# AT32F437.net
KiCad netlist of a schematic drawn in EasyEDA
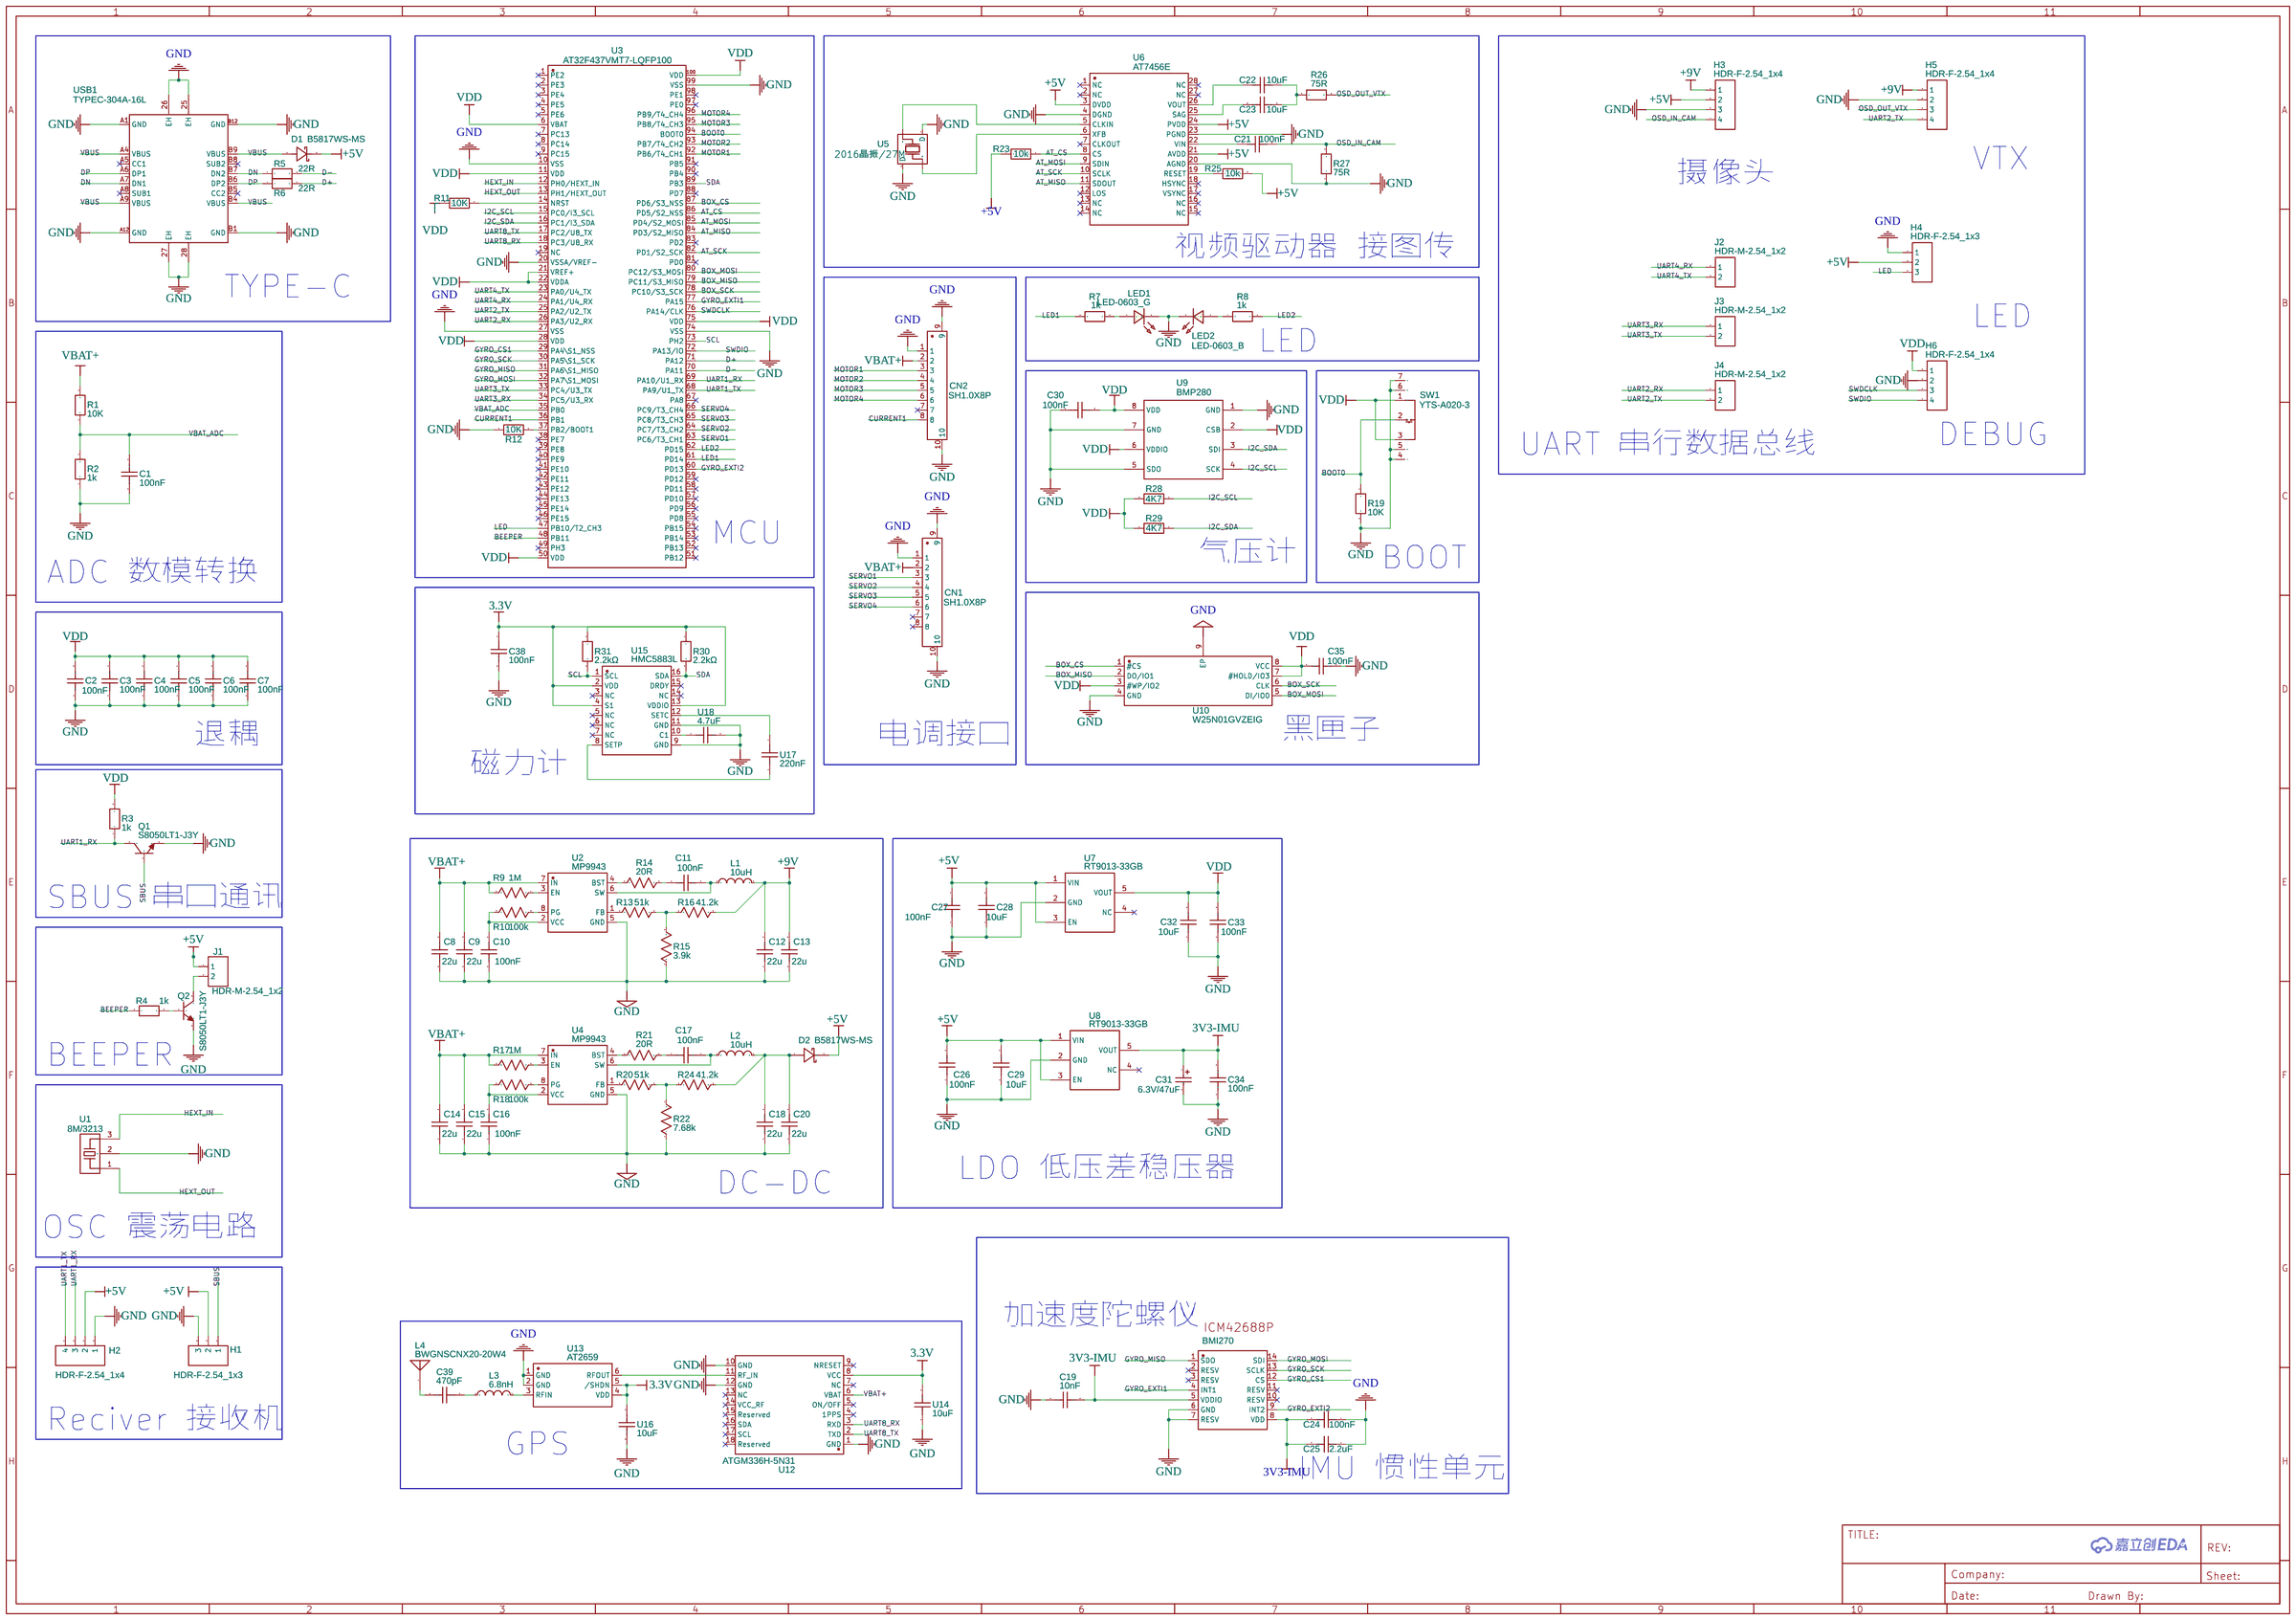
[diagram p0: schematic sheet]

(export (version "E")
  (design (tool "Eeschema 10.0.6"))
  (components
    (comp (ref "C1") (value "100nF") (libsource (lib "") (part "C_0402_US")))
    (comp (ref "C2") (value "100nF") (libsource (lib "") (part "C_0402_US")))
    (comp (ref "C3") (value "100nF") (libsource (lib "") (part "C_0402_US")))
    (comp (ref "C4") (value "100nF") (libsource (lib "") (part "C_0402_US")))
    (comp (ref "C5") (value "100nF") (libsource (lib "") (part "C_0402_US")))
    (comp (ref "C6") (value "100nF") (libsource (lib "") (part "C_0402_US")))
    (comp (ref "C7") (value "100nF") (libsource (lib "") (part "C_0402_US")))
    (comp (ref "C8") (value "22u") (libsource (lib "") (part "C_0201_US")))
    (comp (ref "C9") (value "22u") (libsource (lib "") (part "C_0201_US")))
    (comp (ref "C10") (value "100nF") (libsource (lib "") (part "C_0201_US")))
    (comp (ref "C11") (value "100nF") (libsource (lib "") (part "C_0201_US_1")))
    (comp (ref "C12") (value "22u") (libsource (lib "") (part "C_0201_US")))
    (comp (ref "C13") (value "22u") (libsource (lib "") (part "C_0201_US")))
    (comp (ref "C14") (value "22u") (libsource (lib "") (part "C_0201_US")))
    (comp (ref "C15") (value "22u") (libsource (lib "") (part "C_0201_US")))
    (comp (ref "C16") (value "100nF") (libsource (lib "") (part "C_0201_US")))
    (comp (ref "C17") (value "100nF") (libsource (lib "") (part "C_0201_US_1")))
    (comp (ref "C18") (value "22u") (libsource (lib "") (part "C_0201_US")))
    (comp (ref "C19") (value "10nF") (libsource (lib "") (part "C_0402_US_2")))
    (comp (ref "C20") (value "22u") (libsource (lib "") (part "C_0201_US")))
    (comp (ref "C21") (value "100nF") (libsource (lib "") (part "C_0402_US_2")))
    (comp (ref "C22") (value "10uF") (libsource (lib "") (part "C_0603_US_1")))
    (comp (ref "C23") (value "10uF") (libsource (lib "") (part "C_0603_US_1")))
    (comp (ref "C24") (value "100nF") (libsource (lib "") (part "C_0402_US_1")))
    (comp (ref "C25") (value "2.2uF") (libsource (lib "") (part "C_0402_US_1")))
    (comp (ref "C26") (value "100nF") (libsource (lib "") (part "C_0603_US")))
    (comp (ref "C27") (value "100nF") (libsource (lib "") (part "C_0603_US")))
    (comp (ref "C28") (value "10uF") (libsource (lib "") (part "C_0603_US")))
    (comp (ref "C29") (value "10uF") (libsource (lib "") (part "C_0402_US")))
    (comp (ref "C30") (value "100nF") (libsource (lib "") (part "C_0402_US_2")))
    (comp (ref "C31")
      (value "6.3V/47uF")
      (fields (field (name "Manufacturer Part") "TAJA476K006RNJ") (field (name "Manufacturer") "AVX"))
      (libsource (lib "") (part "TAJA476K006RNJ"))
    )
    (comp (ref "C32") (value "10uF") (libsource (lib "") (part "C_0603_US")))
    (comp (ref "C33") (value "100nF") (libsource (lib "") (part "C_0603_US")))
    (comp (ref "C34") (value "100nF") (libsource (lib "") (part "C_0402_US")))
    (comp (ref "C35") (value "100nF") (libsource (lib "") (part "C_0402_US_2")))
    (comp (ref "C38")
      (value "100nF")
      (fields
        (field (name "Manufacturer Part") "CC0603MRY5V8BB104")
        (field (name "Manufacturer") "YAGEO(国巨)")
      )
      (libsource (lib "") (part "CC0603MRY5V8BB104"))
    )
    (comp (ref "C39")
      (value "470pF")
      (fields (field (name "Manufacturer Part") "FM18X471K101PSG") (field (name "Manufacturer") "PSA(信昌电陶)"))
      (libsource (lib "") (part "FM18X471K101PSG"))
    )
    (comp (ref "CN1")
      (value "SH1.0X8P")
      (fields (field (name "Manufacturer Part") "WAFER_SMT_1.0X8"))
      (libsource (lib "") (part "WAFER_SMT_1.0X8"))
    )
    (comp (ref "CN2")
      (value "SH1.0X8P")
      (fields (field (name "Manufacturer Part") "WAFER_SMT_1.0X8"))
      (libsource (lib "") (part "WAFER_SMT_1.0X8"))
    )
    (comp (ref "D1")
      (value "B5817WS-MS")
      (fields (field (name "Manufacturer") "MSKSEMI(美森科)"))
      (libsource (lib "") (part "B5817WS-MS"))
    )
    (comp (ref "D2")
      (value "B5817WS-MS")
      (fields (field (name "Manufacturer") "MSKSEMI(美森科)"))
      (libsource (lib "") (part "B5817WS-MS"))
    )
    (comp (ref "H1") (value "HDR-F-2.54_1x3") (libsource (lib "") (part "HDR-F-2.54_1x3_1")))
    (comp (ref "H2") (value "HDR-F-2.54_1x4") (libsource (lib "") (part "HDR-F-2.54_1x4_1")))
    (comp (ref "H3") (value "HDR-F-2.54_1x4") (libsource (lib "") (part "HDR-F-2.54_1x4")))
    (comp (ref "H4") (value "HDR-F-2.54_1x3") (libsource (lib "") (part "HDR-F-2.54_1x3")))
    (comp (ref "H5") (value "HDR-F-2.54_1x4") (libsource (lib "") (part "HDR-F-2.54_1x4")))
    (comp (ref "H6") (value "HDR-F-2.54_1x4") (libsource (lib "") (part "HDR-F-2.54_1x4")))
    (comp (ref "J1") (value "HDR-M-2.54_1x2") (libsource (lib "") (part "HDR-M-2.54_1x2")))
    (comp (ref "J2") (value "HDR-M-2.54_1x2") (libsource (lib "") (part "HDR-M-2.54_1x2")))
    (comp (ref "J3") (value "HDR-M-2.54_1x2") (libsource (lib "") (part "HDR-M-2.54_1x2")))
    (comp (ref "J4") (value "HDR-M-2.54_1x2") (libsource (lib "") (part "HDR-M-2.54_1x2")))
    (comp (ref "L1")
      (value "10uH")
      (fields (field (name "Manufacturer Part") "PHC0420-100M-T") (field (name "Manufacturer") "EMTEK"))
      (libsource (lib "") (part "PHC0420-100M-T"))
    )
    (comp (ref "L2")
      (value "10uH")
      (fields (field (name "Manufacturer Part") "PHC0420-100M-T") (field (name "Manufacturer") "EMTEK"))
      (libsource (lib "") (part "PHC0420-100M-T"))
    )
    (comp (ref "L3")
      (value "6.8nH")
      (fields (field (name "Manufacturer Part") "VHF060303H6N8KT") (field (name "Manufacturer") "FH(风华)"))
      (libsource (lib "") (part "VHF060303H6N8KT"))
    )
    (comp (ref "L4")
      (value "BWGNSCNX20-20W4")
      (fields (field (name "Manufacturer") "BAT WIRELESS(蝙蝠无线)"))
      (libsource (lib "") (part "BWGNSCNX20-20W4"))
    )
    (comp (ref "LED1")
      (value "LED-0603_G")
      (fields
        (field (name "Manufacturer Part") "19-217/GHC-YR1S2/3T")
        (field (name "Manufacturer") "EVERLIGHT(台湾亿光)")
      )
      (libsource (lib "") (part "LED-0603_G"))
    )
    (comp (ref "LED2")
      (value "LED-0603_B")
      (fields
        (field (name "Manufacturer Part") "19-217/BHC-ZL1M2RY/3T")
        (field (name "Manufacturer") "EVERLIGHT(台湾亿光)")
      )
      (libsource (lib "") (part "LED-0603_B"))
    )
    (comp (ref "Q1")
      (value "S8050LT1-J3Y")
      (fields (field (name "Manufacturer") "FH(风华)"))
      (libsource (lib "") (part "S8050LT1-J3Y_1"))
    )
    (comp (ref "Q2")
      (value "S8050LT1-J3Y")
      (fields (field (name "Manufacturer") "FH(风华)"))
      (libsource (lib "") (part "S8050LT1-J3Y"))
    )
    (comp (ref "R1") (value "10K") (libsource (lib "") (part "R_0603_EU_1")))
    (comp (ref "R2") (value "1k") (libsource (lib "") (part "R_0603_EU_1")))
    (comp (ref "R3") (value "1k") (libsource (lib "") (part "R_0402_EU_1")))
    (comp (ref "R4") (value "1k") (libsource (lib "") (part "R_0402_EU")))
    (comp (ref "R5") (value "22R") (libsource (lib "") (part "R_0402_EU")))
    (comp (ref "R6") (value "22R") (libsource (lib "") (part "R_0402_EU")))
    (comp (ref "R7") (value "1k") (libsource (lib "") (part "R_0603_EU_3")))
    (comp (ref "R8") (value "1k") (libsource (lib "") (part "R_0603_EU")))
    (comp (ref "R9") (value "1M") (libsource (lib "") (part "R_0201_US_2")))
    (comp (ref "R10") (value "100k") (libsource (lib "") (part "R_0201_US")))
    (comp (ref "R11") (value "10K") (libsource (lib "") (part "R_0603_EU_3")))
    (comp (ref "R12") (value "10K") (libsource (lib "") (part "R_0603_EU")))
    (comp (ref "R13") (value "51k") (libsource (lib "") (part "R_0201_US")))
    (comp (ref "R14") (value "20R") (libsource (lib "") (part "R_0201_US")))
    (comp (ref "R15") (value "3.9k") (libsource (lib "") (part "R_0201_US_1")))
    (comp (ref "R16") (value "41.2k") (libsource (lib "") (part "R_0201_US")))
    (comp (ref "R17") (value "1M") (libsource (lib "") (part "R_0201_US_2")))
    (comp (ref "R18") (value "100k") (libsource (lib "") (part "R_0201_US")))
    (comp (ref "R19") (value "10K") (libsource (lib "") (part "R_0603_EU_2")))
    (comp (ref "R20") (value "51k") (libsource (lib "") (part "R_0201_US")))
    (comp (ref "R21") (value "20R") (libsource (lib "") (part "R_0201_US")))
    (comp (ref "R22") (value "7.68k") (libsource (lib "") (part "R_0201_US_1")))
    (comp (ref "R23") (value "10k") (libsource (lib "") (part "R_0402_EU")))
    (comp (ref "R24") (value "41.2k") (libsource (lib "") (part "R_0201_US")))
    (comp (ref "R25") (value "10k") (libsource (lib "") (part "R_0402_EU")))
    (comp (ref "R26") (value "75R") (libsource (lib "") (part "R_0805_EU")))
    (comp (ref "R27") (value "75R") (libsource (lib "") (part "R_0805_EU_1")))
    (comp (ref "R28") (value "4K7") (libsource (lib "") (part "R_0402_EU_2")))
    (comp (ref "R29") (value "4K7") (libsource (lib "") (part "R_0402_EU_2")))
    (comp (ref "R30")
      (value "2.2kΩ")
      (fields (field (name "Manufacturer Part") "SCR0603J2K2") (field (name "Manufacturer") "VO(翔胜)"))
      (libsource (lib "") (part "SCR0603J2K2"))
    )
    (comp (ref "R31")
      (value "2.2kΩ")
      (fields (field (name "Manufacturer Part") "SCR0603J2K2") (field (name "Manufacturer") "VO(翔胜)"))
      (libsource (lib "") (part "SCR0603J2K2"))
    )
    (comp (ref "SDO1") (value "BMI270") (libsource (lib "") (part "ICM42688-P")))
    (comp (ref "SW1")
      (value "YTS-A020-3")
      (fields (field (name "Manufacturer") "YIYUAN(怡远)"))
      (libsource (lib "") (part "YTS-A020-3"))
    )
    (comp (ref "U1") (value "8M/3213") (libsource (lib "") (part "3213晶振")))
    (comp (ref "U2") (value "MP9943") (libsource (lib "") (part "MP9943")))
    (comp (ref "U3")
      (value "AT32F437VMT7-LQFP100")
      (fields (field (name "Manufacturer Part") "AT32F435VMT7") (field (name "Manufacturer") "ARTERY（雅特力）"))
      (libsource (lib "") (part "AT32F435VGT7"))
    )
    (comp (ref "U4") (value "MP9943") (libsource (lib "") (part "MP9943")))
    (comp (ref "U5") (value "2016晶振/27M") (libsource (lib "") (part "3225晶振")))
    (comp (ref "U6")
      (value "AT7456E")
      (fields (field (name "Manufacturer") "ZHONGKEWEI"))
      (libsource (lib "") (part "AT7456E"))
    )
    (comp (ref "U7")
      (value "RT9013-33GB")
      (fields (field (name "Manufacturer") "RICHTEK"))
      (libsource (lib "") (part "RT9013-33GB"))
    )
    (comp (ref "U8")
      (value "RT9013-33GB")
      (fields (field (name "Manufacturer") "RICHTEK"))
      (libsource (lib "") (part "RT9013-33GB"))
    )
    (comp (ref "U9")
      (value "BMP280")
      (fields (field (name "Manufacturer") "Bosch"))
      (libsource (lib "") (part "BMP280"))
    )
    (comp (ref "U10")
      (value "W25N01GVZEIG")
      (fields (field (name "Manufacturer") "Winbond Elec"))
      (libsource (lib "") (part "W25N01GVZEIG NoHole"))
    )
    (comp (ref "U12")
      (value "ATGM336H-5N31")
      (fields (field (name "Manufacturer") "杭州中科微"))
      (libsource (lib "") (part "ATGM336H-5N31"))
    )
    (comp (ref "U13")
      (value "AT2659")
      (fields (field (name "Manufacturer") "杭州中科微"))
      (libsource (lib "") (part "AT2659"))
    )
    (comp (ref "U14")
      (value "10uF")
      (fields (field (name "Manufacturer Part") "0603X106K100CT") (field (name "Manufacturer") "Walsin(华新科)"))
      (libsource (lib "") (part "0603X106K100CT"))
    )
    (comp (ref "U15") (value "HMC5883L") (libsource (lib "") (part "HMC5883L")))
    (comp (ref "U16")
      (value "10uF")
      (fields (field (name "Manufacturer Part") "0603X106K100CT") (field (name "Manufacturer") "Walsin(华新科)"))
      (libsource (lib "") (part "0603X106K100CT"))
    )
    (comp (ref "U17")
      (value "220nF")
      (fields (field (name "Manufacturer Part") "CGA3E3X5R1V224M080AB") (field (name "Manufacturer") "TDK"))
      (libsource (lib "") (part "CGA3E3X5R1V224M080AB"))
    )
    (comp (ref "U18")
      (value "4.7uF")
      (fields (field (name "Manufacturer Part") "C1005X5R1A475M050BC") (field (name "Manufacturer") "TDK"))
      (libsource (lib "") (part "C1005X5R1A475M050BC"))
    )
    (comp (ref "USB1")
      (value "TYPEC-304A-16L")
      (fields
        (field (name "Manufacturer Part") "TYPEC-304A-ACP16L")
        (field (name "Manufacturer") "XUNPU(讯普)")
      )
      (libsource (lib "") (part "TYPEC-304A-ACP16L"))
    )
  )
  (nets
    (net (code "1") (name "+5V") (class "Default")
      (node (ref "C26") (pin "2") (pinfunction "2_2") (pintype "unspecified"))
      (node (ref "C27") (pin "2") (pinfunction "2_2") (pintype "unspecified"))
      (node (ref "C28") (pin "2") (pinfunction "2_2") (pintype "unspecified"))
      (node (ref "C29") (pin "2") (pinfunction "2_2") (pintype "unspecified"))
      (node (ref "D1") (pin "2") (pinfunction "K_2") (pintype "unspecified"))
      (node (ref "D2") (pin "2") (pinfunction "K_2") (pintype "unspecified"))
      (node (ref "H1") (pin "2") (pinfunction "2_2") (pintype "input"))
      (node (ref "H2") (pin "2") (pinfunction "2_2") (pintype "unspecified"))
      (node (ref "H3") (pin "2") (pinfunction "2_2") (pintype "unspecified"))
      (node (ref "H4") (pin "2") (pinfunction "2_2") (pintype "input"))
      (node (ref "J1") (pin "1") (pinfunction "1_1") (pintype "unspecified"))
      (node (ref "R23") (pin "1") (pinfunction "1_1") (pintype "unspecified"))
      (node (ref "R25") (pin "2") (pinfunction "2_2") (pintype "unspecified"))
      (node (ref "U6") (pin "21") (pinfunction "AVDD_21") (pintype "unspecified"))
      (node (ref "U6") (pin "24") (pinfunction "PVDD_24") (pintype "unspecified"))
      (node (ref "U6") (pin "3") (pinfunction "DVDD_3") (pintype "unspecified"))
      (node (ref "U7") (pin "1") (pinfunction "VIN_1") (pintype "unspecified"))
      (node (ref "U7") (pin "3") (pinfunction "EN_3") (pintype "unspecified"))
      (node (ref "U8") (pin "1") (pinfunction "VIN_1") (pintype "unspecified"))
      (node (ref "U8") (pin "3") (pinfunction "EN_3") (pintype "unspecified"))
    )
    (net (code "2") (name "+9V") (class "Default")
      (node (ref "C12") (pin "2") (pinfunction "2_2") (pintype "unspecified"))
      (node (ref "C13") (pin "2") (pinfunction "2_2") (pintype "unspecified"))
      (node (ref "H3") (pin "1") (pinfunction "1_1") (pintype "unspecified"))
      (node (ref "H5") (pin "1") (pinfunction "1_1") (pintype "unspecified"))
      (node (ref "L1") (pin "2") (pinfunction "2_2") (pintype "unspecified"))
      (node (ref "R16") (pin "2") (pinfunction "2_2") (pintype "unspecified"))
    )
    (net (code "3") (name "/AT_CS") (class "Default")
      (node (ref "R23") (pin "2") (pinfunction "2_2") (pintype "unspecified"))
      (node (ref "U3") (pin "86") (pinfunction "PD5/S2_NSS_86") (pintype "unspecified"))
      (node (ref "U6") (pin "8") (pinfunction "CS_8") (pintype "unspecified"))
    )
    (net (code "4") (name "/AT_MISO") (class "Default")
      (node (ref "U3") (pin "84") (pinfunction "PD3/S2_MISO_84") (pintype "unspecified"))
      (node (ref "U6") (pin "11") (pinfunction "SDOUT_11") (pintype "unspecified"))
    )
    (net (code "5") (name "/AT_MOSI") (class "Default")
      (node (ref "U3") (pin "85") (pinfunction "PD4/S2_MOSI_85") (pintype "unspecified"))
      (node (ref "U6") (pin "9") (pinfunction "SDIN_9") (pintype "unspecified"))
    )
    (net (code "6") (name "/AT_SCK") (class "Default")
      (node (ref "U3") (pin "82") (pinfunction "PD1/S2_SCK_82") (pintype "unspecified"))
      (node (ref "U6") (pin "10") (pinfunction "SCLK_10") (pintype "unspecified"))
    )
    (net (code "7") (name "/BEEPER") (class "Default")
      (node (ref "R4") (pin "1") (pinfunction "1_1") (pintype "unspecified"))
      (node (ref "U3") (pin "48") (pinfunction "PB11_48") (pintype "unspecified"))
    )
    (net (code "8") (name "/BOOT0") (class "Default")
      (node (ref "R19") (pin "1") (pinfunction "1_1") (pintype "unspecified"))
      (node (ref "SW1") (pin "2") (pinfunction "2_2") (pintype "unspecified"))
      (node (ref "U3") (pin "94") (pinfunction "BOOT0_94") (pintype "unspecified"))
    )
    (net (code "9") (name "/BOX_CS") (class "Default")
      (node (ref "U10") (pin "1") (pinfunction "#CS_1") (pintype "unspecified"))
      (node (ref "U3") (pin "87") (pinfunction "PD6/S3_NSS_87") (pintype "unspecified"))
    )
    (net (code "10") (name "/BOX_MISO") (class "Default")
      (node (ref "U10") (pin "2") (pinfunction "DO/IO1_2") (pintype "unspecified"))
      (node (ref "U3") (pin "79") (pinfunction "PC11/S3_MISO_79") (pintype "unspecified"))
    )
    (net (code "11") (name "/BOX_MOSI") (class "Default")
      (node (ref "U10") (pin "5") (pinfunction "DI/IO0_5") (pintype "unspecified"))
      (node (ref "U3") (pin "80") (pinfunction "PC12/S3_MOSI_80") (pintype "unspecified"))
    )
    (net (code "12") (name "/BOX_SCK") (class "Default")
      (node (ref "U10") (pin "6") (pinfunction "CLK_6") (pintype "unspecified"))
      (node (ref "U3") (pin "78") (pinfunction "PC10/S3_SCK_78") (pintype "unspecified"))
    )
    (net (code "13") (name "/CURRENT1") (class "Default")
      (node (ref "CN2") (pin "8") (pinfunction "8_8") (pintype "unspecified"))
      (node (ref "U3") (pin "36") (pinfunction "PB1_36") (pintype "unspecified"))
    )
    (net (code "14") (name "/D+") (class "Default")
      (node (ref "R6") (pin "2") (pinfunction "2_2") (pintype "unspecified"))
      (node (ref "U3") (pin "71") (pinfunction "PA12_71") (pintype "unspecified"))
    )
    (net (code "15") (name "/D-") (class "Default")
      (node (ref "R5") (pin "2") (pinfunction "2_2") (pintype "unspecified"))
      (node (ref "U3") (pin "70") (pinfunction "PA11_70") (pintype "unspecified"))
    )
    (net (code "16") (name "/DN") (class "Default")
      (node (ref "R5") (pin "1") (pinfunction "1_1") (pintype "unspecified"))
      (node (ref "USB1") (pin "A7") (pinfunction "DN1_A7") (pintype "unspecified"))
      (node (ref "USB1") (pin "B7") (pinfunction "DN2_B7") (pintype "unspecified"))
    )
    (net (code "17") (name "/DP") (class "Default")
      (node (ref "R6") (pin "1") (pinfunction "1_1") (pintype "unspecified"))
      (node (ref "USB1") (pin "A6") (pinfunction "DP1_A6") (pintype "unspecified"))
      (node (ref "USB1") (pin "B6") (pinfunction "DP2_B6") (pintype "unspecified"))
    )
    (net (code "18") (name "/GYRO_CS1") (class "Default")
      (node (ref "SDO1") (pin "12") (pinfunction "CS_12") (pintype "unspecified"))
      (node (ref "U3") (pin "29") (pinfunction "PA4\\S1_NSS_29") (pintype "unspecified"))
    )
    (net (code "19") (name "/GYRO_EXTI1") (class "Default")
      (node (ref "SDO1") (pin "4") (pinfunction "INT1_4") (pintype "unspecified"))
      (node (ref "U3") (pin "77") (pinfunction "PA15_77") (pintype "unspecified"))
    )
    (net (code "20") (name "/GYRO_EXTI2") (class "Default")
      (node (ref "SDO1") (pin "9") (pinfunction "INT2_9") (pintype "unspecified"))
      (node (ref "U3") (pin "60") (pinfunction "PD13_60") (pintype "unspecified"))
    )
    (net (code "21") (name "/GYRO_MISO") (class "Default")
      (node (ref "SDO1") (pin "1") (pinfunction "SDO_1") (pintype "unspecified"))
      (node (ref "U3") (pin "31") (pinfunction "PA6\\S1_MISO_31") (pintype "unspecified"))
    )
    (net (code "22") (name "/GYRO_MOSI") (class "Default")
      (node (ref "SDO1") (pin "14") (pinfunction "SDI_14") (pintype "unspecified"))
      (node (ref "U3") (pin "32") (pinfunction "PA7\\S1_MOSI_32") (pintype "unspecified"))
    )
    (net (code "23") (name "/GYRO_SCK") (class "Default")
      (node (ref "SDO1") (pin "13") (pinfunction "SCLK_13") (pintype "unspecified"))
      (node (ref "U3") (pin "30") (pinfunction "PA5\\S1_SCK_30") (pintype "unspecified"))
    )
    (net (code "24") (name "/HEXT_IN") (class "Default")
      (node (ref "U1") (pin "3") (pinfunction "3_3") (pintype "unspecified"))
      (node (ref "U3") (pin "12") (pinfunction "PH0/HEXT_IN_12") (pintype "unspecified"))
    )
    (net (code "25") (name "/HEXT_OUT") (class "Default")
      (node (ref "U1") (pin "1") (pinfunction "1_1") (pintype "unspecified"))
      (node (ref "U3") (pin "13") (pinfunction "PH1/HEXT_OUT_13") (pintype "unspecified"))
    )
    (net (code "26") (name "/I2C_SCL") (class "Default")
      (node (ref "R28") (pin "1") (pinfunction "1_1") (pintype "unspecified"))
      (node (ref "U3") (pin "15") (pinfunction "PC0/I3_SCL_15") (pintype "unspecified"))
      (node (ref "U9") (pin "4") (pinfunction "SCK_4") (pintype "unspecified"))
    )
    (net (code "27") (name "/I2C_SDA") (class "Default")
      (node (ref "R29") (pin "1") (pinfunction "1_1") (pintype "unspecified"))
      (node (ref "U3") (pin "16") (pinfunction "PC1/I3_SDA_16") (pintype "unspecified"))
      (node (ref "U9") (pin "3") (pinfunction "SDI_3") (pintype "unspecified"))
    )
    (net (code "28") (name "/LED") (class "Default")
      (node (ref "H4") (pin "3") (pinfunction "3_3") (pintype "input"))
      (node (ref "U3") (pin "47") (pinfunction "PB10/T2_CH3_47") (pintype "unspecified"))
    )
    (net (code "29") (name "/LED1") (class "Default")
      (node (ref "R7") (pin "2") (pinfunction "2_2") (pintype "unspecified"))
      (node (ref "U3") (pin "61") (pinfunction "PD14_61") (pintype "unspecified"))
    )
    (net (code "30") (name "/LED2") (class "Default")
      (node (ref "R8") (pin "2") (pinfunction "2_2") (pintype "unspecified"))
      (node (ref "U3") (pin "62") (pinfunction "PD15_62") (pintype "unspecified"))
    )
    (net (code "31") (name "/MOTOR1") (class "Default")
      (node (ref "CN2") (pin "3") (pinfunction "3_3") (pintype "unspecified"))
      (node (ref "U3") (pin "92") (pinfunction "PB6/T4_CH1_92") (pintype "unspecified"))
    )
    (net (code "32") (name "/MOTOR2") (class "Default")
      (node (ref "CN2") (pin "4") (pinfunction "4_4") (pintype "unspecified"))
      (node (ref "U3") (pin "93") (pinfunction "PB7/T4_CH2_93") (pintype "unspecified"))
    )
    (net (code "33") (name "/MOTOR3") (class "Default")
      (node (ref "CN2") (pin "5") (pinfunction "5_5") (pintype "unspecified"))
      (node (ref "U3") (pin "95") (pinfunction "PB8/T4_CH3_95") (pintype "unspecified"))
    )
    (net (code "34") (name "/MOTOR4") (class "Default")
      (node (ref "CN2") (pin "6") (pinfunction "6_6") (pintype "unspecified"))
      (node (ref "U3") (pin "96") (pinfunction "PB9/T4_CH4_96") (pintype "unspecified"))
    )
    (net (code "35") (name "/OSD_IN_CAM") (class "Default")
      (node (ref "C21") (pin "2") (pinfunction "2_2") (pintype "unspecified"))
      (node (ref "H3") (pin "4") (pinfunction "4_4") (pintype "unspecified"))
      (node (ref "R27") (pin "2") (pinfunction "2_2") (pintype "unspecified"))
    )
    (net (code "36") (name "/OSD_OUT_VTX") (class "Default")
      (node (ref "H5") (pin "3") (pinfunction "3_3") (pintype "unspecified"))
      (node (ref "R26") (pin "2") (pinfunction "2_2") (pintype "unspecified"))
    )
    (net (code "37") (name "/SBUS") (class "Default")
      (node (ref "H1") (pin "1") (pinfunction "1_1") (pintype "input"))
      (node (ref "Q1") (pin "1") (pinfunction "1_1") (pintype "input"))
    )
    (net (code "38") (name "/SCL") (class "Default")
      (node (ref "R31") (pin "2") (pinfunction "2_2") (pintype "unspecified"))
      (node (ref "U15") (pin "1") (pinfunction "SCL_1") (pintype "unspecified"))
      (node (ref "U3") (pin "73") (pinfunction "PH2_73") (pintype "unspecified"))
    )
    (net (code "39") (name "/SDA") (class "Default")
      (node (ref "R30") (pin "2") (pinfunction "2_2") (pintype "unspecified"))
      (node (ref "U15") (pin "16") (pinfunction "SDA_16") (pintype "unspecified"))
      (node (ref "U3") (pin "89") (pinfunction "PB3_89") (pintype "unspecified"))
    )
    (net (code "40") (name "/SERVO1") (class "Default")
      (node (ref "CN1") (pin "3") (pinfunction "3_3") (pintype "unspecified"))
      (node (ref "U3") (pin "63") (pinfunction "PC6/T3_CH1_63") (pintype "unspecified"))
    )
    (net (code "41") (name "/SERVO2") (class "Default")
      (node (ref "CN1") (pin "4") (pinfunction "4_4") (pintype "unspecified"))
      (node (ref "U3") (pin "64") (pinfunction "PC7/T3_CH2_64") (pintype "unspecified"))
    )
    (net (code "42") (name "/SERVO3") (class "Default")
      (node (ref "CN1") (pin "5") (pinfunction "5_5") (pintype "unspecified"))
      (node (ref "U3") (pin "65") (pinfunction "PC8/T3_CH3_65") (pintype "unspecified"))
    )
    (net (code "43") (name "/SERVO4") (class "Default")
      (node (ref "CN1") (pin "6") (pinfunction "6_6") (pintype "unspecified"))
      (node (ref "U3") (pin "66") (pinfunction "PC9/T3_CH4_66") (pintype "unspecified"))
    )
    (net (code "44") (name "/SWDCLK") (class "Default")
      (node (ref "H6") (pin "3") (pinfunction "3_3") (pintype "unspecified"))
      (node (ref "U3") (pin "76") (pinfunction "PA14/CLK_76") (pintype "unspecified"))
    )
    (net (code "45") (name "/SWDIO") (class "Default")
      (node (ref "H6") (pin "4") (pinfunction "4_4") (pintype "unspecified"))
      (node (ref "U3") (pin "72") (pinfunction "PA13/IO_72") (pintype "unspecified"))
    )
    (net (code "46") (name "/UART1_RX") (class "Default")
      (node (ref "H2") (pin "3") (pinfunction "3_3") (pintype "unspecified"))
      (node (ref "Q1") (pin "3") (pinfunction "3_3") (pintype "input"))
      (node (ref "R3") (pin "1") (pinfunction "1_1") (pintype "unspecified"))
      (node (ref "U3") (pin "69") (pinfunction "PA10/U1_RX_69") (pintype "unspecified"))
    )
    (net (code "47") (name "/UART1_TX") (class "Default")
      (node (ref "H2") (pin "4") (pinfunction "4_4") (pintype "unspecified"))
      (node (ref "U3") (pin "68") (pinfunction "PA9/U1_TX_68") (pintype "unspecified"))
    )
    (net (code "48") (name "/UART2_RX") (class "Default")
      (node (ref "J4") (pin "1") (pinfunction "1_1") (pintype "unspecified"))
      (node (ref "U3") (pin "26") (pinfunction "PA3/U2_RX_26") (pintype "unspecified"))
    )
    (net (code "49") (name "/UART2_TX") (class "Default")
      (node (ref "H5") (pin "4") (pinfunction "4_4") (pintype "unspecified"))
      (node (ref "J4") (pin "2") (pinfunction "2_2") (pintype "unspecified"))
      (node (ref "U3") (pin "25") (pinfunction "PA2/U2_TX_25") (pintype "unspecified"))
    )
    (net (code "50") (name "/UART3_RX") (class "Default")
      (node (ref "J3") (pin "1") (pinfunction "1_1") (pintype "unspecified"))
      (node (ref "U3") (pin "34") (pinfunction "PC5/U3_RX_34") (pintype "unspecified"))
    )
    (net (code "51") (name "/UART3_TX") (class "Default")
      (node (ref "J3") (pin "2") (pinfunction "2_2") (pintype "unspecified"))
      (node (ref "U3") (pin "33") (pinfunction "PC4/U3_TX_33") (pintype "unspecified"))
    )
    (net (code "52") (name "/UART4_RX") (class "Default")
      (node (ref "J2") (pin "1") (pinfunction "1_1") (pintype "unspecified"))
      (node (ref "U3") (pin "24") (pinfunction "PA1/U4_RX_24") (pintype "unspecified"))
    )
    (net (code "53") (name "/UART4_TX") (class "Default")
      (node (ref "J2") (pin "2") (pinfunction "2_2") (pintype "unspecified"))
      (node (ref "U3") (pin "23") (pinfunction "PA0/U4_TX_23") (pintype "unspecified"))
    )
    (net (code "54") (name "/UART8_RX") (class "Default")
      (node (ref "U12") (pin "3") (pinfunction "RXD_3") (pintype "unspecified"))
      (node (ref "U3") (pin "18") (pinfunction "PC3/U8_RX_18") (pintype "unspecified"))
    )
    (net (code "55") (name "/UART8_TX") (class "Default")
      (node (ref "U12") (pin "2") (pinfunction "TXD_2") (pintype "unspecified"))
      (node (ref "U3") (pin "17") (pinfunction "PC2/U8_TX_17") (pintype "unspecified"))
    )
    (net (code "56") (name "/VBAT_ADC") (class "Default")
      (node (ref "C1") (pin "2") (pinfunction "2_2") (pintype "unspecified"))
      (node (ref "R1") (pin "1") (pinfunction "1_1") (pintype "unspecified"))
      (node (ref "R2") (pin "2") (pinfunction "2_2") (pintype "unspecified"))
      (node (ref "U3") (pin "35") (pinfunction "PB0_35") (pintype "unspecified"))
    )
    (net (code "57") (name "/VBUS") (class "Default")
      (node (ref "D1") (pin "1") (pinfunction "A_1") (pintype "unspecified"))
      (node (ref "USB1") (pin "A4") (pinfunction "VBUS_A4") (pintype "unspecified"))
      (node (ref "USB1") (pin "A9") (pinfunction "VBUS_A9") (pintype "unspecified"))
      (node (ref "USB1") (pin "B4") (pinfunction "VBUS_B4") (pintype "unspecified"))
      (node (ref "USB1") (pin "B9") (pinfunction "VBUS_B9") (pintype "unspecified"))
    )
    (net (code "58") (name "3.3V") (class "Default")
      (node (ref "C38") (pin "1") (pinfunction "1_1") (pintype "unspecified"))
      (node (ref "R30") (pin "1") (pinfunction "1_1") (pintype "unspecified"))
      (node (ref "R31") (pin "1") (pinfunction "1_1") (pintype "unspecified"))
      (node (ref "U12") (pin "8") (pinfunction "VCC_8") (pintype "unspecified"))
      (node (ref "U13") (pin "4") (pinfunction "VDD_4") (pintype "unspecified"))
      (node (ref "U13") (pin "5") (pinfunction "/SHDN_5") (pintype "unspecified"))
      (node (ref "U14") (pin "1") (pinfunction "1_1") (pintype "unspecified"))
      (node (ref "U15") (pin "13") (pinfunction "VDDIO_13") (pintype "unspecified"))
      (node (ref "U15") (pin "2") (pinfunction "VDD_2") (pintype "unspecified"))
      (node (ref "U15") (pin "4") (pinfunction "S1_4") (pintype "unspecified"))
      (node (ref "U16") (pin "1") (pinfunction "1_1") (pintype "unspecified"))
    )
    (net (code "59") (name "3V3-IMU") (class "Default")
      (node (ref "C19") (pin "2") (pinfunction "2_2") (pintype "unspecified"))
      (node (ref "C24") (pin "2") (pinfunction "2_2") (pintype "unspecified"))
      (node (ref "C25") (pin "2") (pinfunction "2_2") (pintype "unspecified"))
      (node (ref "C31") (pin "1") (pinfunction "1_1") (pintype "input"))
      (node (ref "C34") (pin "2") (pinfunction "2_2") (pintype "unspecified"))
      (node (ref "SDO1") (pin "5") (pinfunction "VDDIO_5") (pintype "unspecified"))
      (node (ref "SDO1") (pin "8") (pinfunction "VDD_8") (pintype "unspecified"))
      (node (ref "U8") (pin "5") (pinfunction "VOUT_5") (pintype "unspecified"))
    )
    (net (code "60") (name "GND") (class "Default")
      (node (ref "C1") (pin "1") (pinfunction "1_1") (pintype "unspecified"))
      (node (ref "C10") (pin "1") (pinfunction "1_1") (pintype "unspecified"))
      (node (ref "C12") (pin "1") (pinfunction "1_1") (pintype "unspecified"))
      (node (ref "C13") (pin "1") (pinfunction "1_1") (pintype "unspecified"))
      (node (ref "C14") (pin "1") (pinfunction "1_1") (pintype "unspecified"))
      (node (ref "C15") (pin "1") (pinfunction "1_1") (pintype "unspecified"))
      (node (ref "C16") (pin "1") (pinfunction "1_1") (pintype "unspecified"))
      (node (ref "C18") (pin "1") (pinfunction "1_1") (pintype "unspecified"))
      (node (ref "C19") (pin "1") (pinfunction "1_1") (pintype "unspecified"))
      (node (ref "C2") (pin "1") (pinfunction "1_1") (pintype "unspecified"))
      (node (ref "C20") (pin "1") (pinfunction "1_1") (pintype "unspecified"))
      (node (ref "C24") (pin "1") (pinfunction "1_1") (pintype "unspecified"))
      (node (ref "C25") (pin "1") (pinfunction "1_1") (pintype "unspecified"))
      (node (ref "C26") (pin "1") (pinfunction "1_1") (pintype "unspecified"))
      (node (ref "C27") (pin "1") (pinfunction "1_1") (pintype "unspecified"))
      (node (ref "C28") (pin "1") (pinfunction "1_1") (pintype "unspecified"))
      (node (ref "C29") (pin "1") (pinfunction "1_1") (pintype "unspecified"))
      (node (ref "C3") (pin "1") (pinfunction "1_1") (pintype "unspecified"))
      (node (ref "C30") (pin "1") (pinfunction "1_1") (pintype "unspecified"))
      (node (ref "C31") (pin "2") (pinfunction "2_2") (pintype "input"))
      (node (ref "C32") (pin "1") (pinfunction "1_1") (pintype "unspecified"))
      (node (ref "C33") (pin "1") (pinfunction "1_1") (pintype "unspecified"))
      (node (ref "C34") (pin "1") (pinfunction "1_1") (pintype "unspecified"))
      (node (ref "C35") (pin "2") (pinfunction "2_2") (pintype "unspecified"))
      (node (ref "C38") (pin "2") (pinfunction "2_2") (pintype "unspecified"))
      (node (ref "C4") (pin "1") (pinfunction "1_1") (pintype "unspecified"))
      (node (ref "C5") (pin "1") (pinfunction "1_1") (pintype "unspecified"))
      (node (ref "C6") (pin "1") (pinfunction "1_1") (pintype "unspecified"))
      (node (ref "C7") (pin "1") (pinfunction "1_1") (pintype "unspecified"))
      (node (ref "C8") (pin "1") (pinfunction "1_1") (pintype "unspecified"))
      (node (ref "C9") (pin "1") (pinfunction "1_1") (pintype "unspecified"))
      (node (ref "CN1") (pin "1") (pinfunction "1_1") (pintype "unspecified"))
      (node (ref "CN1") (pin "10") (pinfunction "10_10") (pintype "unspecified"))
      (node (ref "CN1") (pin "9") (pinfunction "9_9") (pintype "unspecified"))
      (node (ref "CN2") (pin "1") (pinfunction "1_1") (pintype "unspecified"))
      (node (ref "CN2") (pin "10") (pinfunction "10_10") (pintype "unspecified"))
      (node (ref "CN2") (pin "9") (pinfunction "9_9") (pintype "unspecified"))
      (node (ref "H1") (pin "3") (pinfunction "3_3") (pintype "input"))
      (node (ref "H2") (pin "1") (pinfunction "1_1") (pintype "unspecified"))
      (node (ref "H3") (pin "3") (pinfunction "3_3") (pintype "unspecified"))
      (node (ref "H4") (pin "1") (pinfunction "1_1") (pintype "input"))
      (node (ref "H5") (pin "2") (pinfunction "2_2") (pintype "unspecified"))
      (node (ref "H6") (pin "2") (pinfunction "2_2") (pintype "unspecified"))
      (node (ref "LED1") (pin "2") (pinfunction "2_2") (pintype "unspecified"))
      (node (ref "LED2") (pin "2") (pinfunction "2_2") (pintype "unspecified"))
      (node (ref "Q1") (pin "2") (pinfunction "2_2") (pintype "input"))
      (node (ref "Q2") (pin "2") (pinfunction "2_2") (pintype "input"))
      (node (ref "R12") (pin "1") (pinfunction "1_1") (pintype "unspecified"))
      (node (ref "R15") (pin "1") (pinfunction "1_1") (pintype "unspecified"))
      (node (ref "R19") (pin "2") (pinfunction "2_2") (pintype "unspecified"))
      (node (ref "R2") (pin "1") (pinfunction "1_1") (pintype "unspecified"))
      (node (ref "R22") (pin "1") (pinfunction "1_1") (pintype "unspecified"))
      (node (ref "R27") (pin "1") (pinfunction "1_1") (pintype "unspecified"))
      (node (ref "SDO1") (pin "6") (pinfunction "GND_6") (pintype "unspecified"))
      (node (ref "SDO1") (pin "7") (pinfunction "RESV_7") (pintype "unspecified"))
      (node (ref "SW1") (pin "4") (pinfunction "4_4") (pintype "unspecified"))
      (node (ref "SW1") (pin "5") (pinfunction "5_5") (pintype "unspecified"))
      (node (ref "SW1") (pin "6") (pinfunction "6_6") (pintype "unspecified"))
      (node (ref "SW1") (pin "7") (pinfunction "7_7") (pintype "unspecified"))
      (node (ref "U1") (pin "2") (pinfunction "2_2") (pintype "unspecified"))
      (node (ref "U10") (pin "4") (pinfunction "GND_4") (pintype "unspecified"))
      (node (ref "U10") (pin "9") (pinfunction "EP_9") (pintype "unspecified"))
      (node (ref "U12") (pin "1") (pinfunction "GND_1") (pintype "unspecified"))
      (node (ref "U12") (pin "10") (pinfunction "GND_10") (pintype "unspecified"))
      (node (ref "U12") (pin "12") (pinfunction "GND_12") (pintype "unspecified"))
      (node (ref "U13") (pin "1") (pinfunction "GND_1") (pintype "unspecified"))
      (node (ref "U13") (pin "2") (pinfunction "GND_2") (pintype "unspecified"))
      (node (ref "U14") (pin "2") (pinfunction "2_2") (pintype "unspecified"))
      (node (ref "U15") (pin "11") (pinfunction "GND_11") (pintype "unspecified"))
      (node (ref "U15") (pin "9") (pinfunction "GND_9") (pintype "unspecified"))
      (node (ref "U16") (pin "2") (pinfunction "2_2") (pintype "unspecified"))
      (node (ref "U18") (pin "2") (pinfunction "2_2") (pintype "unspecified"))
      (node (ref "U2") (pin "5") (pinfunction "GND_5") (pintype "unspecified"))
      (node (ref "U3") (pin "10") (pinfunction "VSS_10") (pintype "unspecified"))
      (node (ref "U3") (pin "20") (pinfunction "VSSA/VREF-_20") (pintype "unspecified"))
      (node (ref "U3") (pin "27") (pinfunction "VSS_27") (pintype "unspecified"))
      (node (ref "U3") (pin "74") (pinfunction "VSS_74") (pintype "unspecified"))
      (node (ref "U3") (pin "99") (pinfunction "VSS_99") (pintype "unspecified"))
      (node (ref "U4") (pin "5") (pinfunction "GND_5") (pintype "unspecified"))
      (node (ref "U5") (pin "2") (pinfunction "D_2") (pintype "input"))
      (node (ref "U5") (pin "4") (pinfunction "D_4") (pintype "input"))
      (node (ref "U6") (pin "20") (pinfunction "AGND_20") (pintype "unspecified"))
      (node (ref "U6") (pin "23") (pinfunction "PGND_23") (pintype "unspecified"))
      (node (ref "U6") (pin "4") (pinfunction "DGND_4") (pintype "unspecified"))
      (node (ref "U7") (pin "2") (pinfunction "GND_2") (pintype "unspecified"))
      (node (ref "U8") (pin "2") (pinfunction "GND_2") (pintype "unspecified"))
      (node (ref "U9") (pin "1") (pinfunction "GND_1") (pintype "unspecified"))
      (node (ref "U9") (pin "5") (pinfunction "SDO_5") (pintype "unspecified"))
      (node (ref "U9") (pin "7") (pinfunction "GND_7") (pintype "unspecified"))
      (node (ref "USB1") (pin "25") (pinfunction "EH_25") (pintype "unspecified"))
      (node (ref "USB1") (pin "26") (pinfunction "EH_26") (pintype "unspecified"))
      (node (ref "USB1") (pin "27") (pinfunction "EH_27") (pintype "unspecified"))
      (node (ref "USB1") (pin "28") (pinfunction "EH_28") (pintype "unspecified"))
      (node (ref "USB1") (pin "A1") (pinfunction "GND_A1") (pintype "unspecified"))
      (node (ref "USB1") (pin "A12") (pinfunction "GND_A12") (pintype "unspecified"))
      (node (ref "USB1") (pin "B1") (pinfunction "GND_B1") (pintype "unspecified"))
      (node (ref "USB1") (pin "B12") (pinfunction "GND_B12") (pintype "unspecified"))
    )
    (net (code "61") (name "Net-(C11-Pad1)") (class "Default")
      (node (ref "C11") (pin "1") (pinfunction "1_1") (pintype "unspecified"))
      (node (ref "R14") (pin "2") (pinfunction "2_2") (pintype "unspecified"))
    )
    (net (code "62") (name "Net-(C17-Pad1)") (class "Default")
      (node (ref "C17") (pin "1") (pinfunction "1_1") (pintype "unspecified"))
      (node (ref "R21") (pin "2") (pinfunction "2_2") (pintype "unspecified"))
    )
    (net (code "63") (name "Net-(C22-Pad1)") (class "Default")
      (node (ref "C22") (pin "1") (pinfunction "1_1") (pintype "unspecified"))
      (node (ref "C23") (pin "1") (pinfunction "1_1") (pintype "unspecified"))
      (node (ref "R26") (pin "1") (pinfunction "1_1") (pintype "unspecified"))
    )
    (net (code "64") (name "Net-(C39-Pad1)") (class "Default")
      (node (ref "C39") (pin "1") (pinfunction "1_1") (pintype "unspecified"))
      (node (ref "L3") (pin "1") (pinfunction "1_1") (pintype "unspecified"))
    )
    (net (code "65") (name "Net-(C39-Pad2)") (class "Default")
      (node (ref "C39") (pin "2") (pinfunction "2_2") (pintype "unspecified"))
      (node (ref "L4") (pin "1") (pinfunction "1_1") (pintype "unspecified"))
    )
    (net (code "66") (name "Net-(D2-A)") (class "Default")
      (node (ref "C18") (pin "2") (pinfunction "2_2") (pintype "unspecified"))
      (node (ref "C20") (pin "2") (pinfunction "2_2") (pintype "unspecified"))
      (node (ref "D2") (pin "1") (pinfunction "A_1") (pintype "unspecified"))
      (node (ref "L2") (pin "2") (pinfunction "2_2") (pintype "unspecified"))
      (node (ref "R24") (pin "2") (pinfunction "2_2") (pintype "unspecified"))
    )
    (net (code "67") (name "Net-(J1-Pad2)") (class "Default")
      (node (ref "J1") (pin "2") (pinfunction "2_2") (pintype "unspecified"))
      (node (ref "Q2") (pin "3") (pinfunction "3_3") (pintype "input"))
    )
    (net (code "68") (name "Net-(LED1-Pad1)") (class "Default")
      (node (ref "LED1") (pin "1") (pinfunction "1_1") (pintype "unspecified"))
      (node (ref "R7") (pin "1") (pinfunction "1_1") (pintype "unspecified"))
    )
    (net (code "69") (name "Net-(LED2-Pad1)") (class "Default")
      (node (ref "LED2") (pin "1") (pinfunction "1_1") (pintype "unspecified"))
      (node (ref "R8") (pin "1") (pinfunction "1_1") (pintype "unspecified"))
    )
    (net (code "70") (name "Net-(Q2-Pad1)") (class "Default")
      (node (ref "Q2") (pin "1") (pinfunction "1_1") (pintype "input"))
      (node (ref "R4") (pin "2") (pinfunction "2_2") (pintype "unspecified"))
    )
    (net (code "71") (name "Net-(R13-Pad2)") (class "Default")
      (node (ref "R13") (pin "2") (pinfunction "2_2") (pintype "unspecified"))
      (node (ref "R15") (pin "2") (pinfunction "2_2") (pintype "unspecified"))
      (node (ref "R16") (pin "1") (pinfunction "1_1") (pintype "unspecified"))
    )
    (net (code "72") (name "Net-(R20-Pad2)") (class "Default")
      (node (ref "R20") (pin "2") (pinfunction "2_2") (pintype "unspecified"))
      (node (ref "R22") (pin "2") (pinfunction "2_2") (pintype "unspecified"))
      (node (ref "R24") (pin "1") (pinfunction "1_1") (pintype "unspecified"))
    )
    (net (code "73") (name "Net-(U2-BST)") (class "Default")
      (node (ref "R14") (pin "1") (pinfunction "1_1") (pintype "unspecified"))
      (node (ref "U2") (pin "4") (pinfunction "BST_4") (pintype "unspecified"))
    )
    (net (code "74") (name "Net-(U2-EN)") (class "Default")
      (node (ref "R9") (pin "1") (pinfunction "1_1") (pintype "unspecified"))
      (node (ref "U2") (pin "3") (pinfunction "EN_3") (pintype "unspecified"))
    )
    (net (code "75") (name "Net-(U2-FB)") (class "Default")
      (node (ref "R13") (pin "1") (pinfunction "1_1") (pintype "unspecified"))
      (node (ref "U2") (pin "1") (pinfunction "FB_1") (pintype "unspecified"))
    )
    (net (code "76") (name "Net-(U2-PG)") (class "Default")
      (node (ref "R10") (pin "2") (pinfunction "2_2") (pintype "unspecified"))
      (node (ref "U2") (pin "8") (pinfunction "PG_8") (pintype "unspecified"))
    )
    (net (code "77") (name "Net-(U2-SW)") (class "Default")
      (node (ref "C11") (pin "2") (pinfunction "2_2") (pintype "unspecified"))
      (node (ref "L1") (pin "1") (pinfunction "1_1") (pintype "unspecified"))
      (node (ref "U2") (pin "6") (pinfunction "SW_6") (pintype "unspecified"))
    )
    (net (code "78") (name "Net-(U2-VCC)") (class "Default")
      (node (ref "C10") (pin "2") (pinfunction "2_2") (pintype "unspecified"))
      (node (ref "R10") (pin "1") (pinfunction "1_1") (pintype "unspecified"))
      (node (ref "U2") (pin "2") (pinfunction "VCC_2") (pintype "unspecified"))
    )
    (net (code "79") (name "Net-(U3-NRST)") (class "Default")
      (node (ref "R11") (pin "1") (pinfunction "1_1") (pintype "unspecified"))
      (node (ref "U3") (pin "14") (pinfunction "NRST_14") (pintype "unspecified"))
    )
    (net (code "80") (name "Net-(U3-PB2{slash}BOOT1)") (class "Default")
      (node (ref "R12") (pin "2") (pinfunction "2_2") (pintype "unspecified"))
      (node (ref "U3") (pin "37") (pinfunction "PB2/BOOT1_37") (pintype "unspecified"))
    )
    (net (code "81") (name "Net-(U4-BST)") (class "Default")
      (node (ref "R21") (pin "1") (pinfunction "1_1") (pintype "unspecified"))
      (node (ref "U4") (pin "4") (pinfunction "BST_4") (pintype "unspecified"))
    )
    (net (code "82") (name "Net-(U4-EN)") (class "Default")
      (node (ref "R17") (pin "1") (pinfunction "1_1") (pintype "unspecified"))
      (node (ref "U4") (pin "3") (pinfunction "EN_3") (pintype "unspecified"))
    )
    (net (code "83") (name "Net-(U4-FB)") (class "Default")
      (node (ref "R20") (pin "1") (pinfunction "1_1") (pintype "unspecified"))
      (node (ref "U4") (pin "1") (pinfunction "FB_1") (pintype "unspecified"))
    )
    (net (code "84") (name "Net-(U4-PG)") (class "Default")
      (node (ref "R18") (pin "2") (pinfunction "2_2") (pintype "unspecified"))
      (node (ref "U4") (pin "8") (pinfunction "PG_8") (pintype "unspecified"))
    )
    (net (code "85") (name "Net-(U4-SW)") (class "Default")
      (node (ref "C17") (pin "2") (pinfunction "2_2") (pintype "unspecified"))
      (node (ref "L2") (pin "1") (pinfunction "1_1") (pintype "unspecified"))
      (node (ref "U4") (pin "6") (pinfunction "SW_6") (pintype "unspecified"))
    )
    (net (code "86") (name "Net-(U4-VCC)") (class "Default")
      (node (ref "C16") (pin "2") (pinfunction "2_2") (pintype "unspecified"))
      (node (ref "R18") (pin "1") (pinfunction "1_1") (pintype "unspecified"))
      (node (ref "U4") (pin "2") (pinfunction "VCC_2") (pintype "unspecified"))
    )
    (net (code "87") (name "Net-(U5-OSC1)") (class "Default")
      (node (ref "U5") (pin "1") (pinfunction "OSC1_1") (pintype "input"))
      (node (ref "U6") (pin "5") (pinfunction "CLKIN_5") (pintype "unspecified"))
    )
    (net (code "88") (name "Net-(U5-OSC2)") (class "Default")
      (node (ref "U5") (pin "3") (pinfunction "OSC2_3") (pintype "input"))
      (node (ref "U6") (pin "6") (pinfunction "XFB_6") (pintype "unspecified"))
    )
    (net (code "89") (name "Net-(U6-RESET)") (class "Default")
      (node (ref "R25") (pin "1") (pinfunction "1_1") (pintype "unspecified"))
      (node (ref "U6") (pin "19") (pinfunction "RESET_19") (pintype "unspecified"))
    )
    (net (code "90") (name "Net-(U6-SAG)") (class "Default")
      (node (ref "C23") (pin "2") (pinfunction "2_2") (pintype "unspecified"))
      (node (ref "U6") (pin "25") (pinfunction "SAG_25") (pintype "unspecified"))
    )
    (net (code "91") (name "Net-(U6-VIN)") (class "Default")
      (node (ref "C21") (pin "1") (pinfunction "1_1") (pintype "unspecified"))
      (node (ref "U6") (pin "22") (pinfunction "VIN_22") (pintype "unspecified"))
    )
    (net (code "92") (name "Net-(U6-VOUT)") (class "Default")
      (node (ref "C22") (pin "2") (pinfunction "2_2") (pintype "unspecified"))
      (node (ref "U6") (pin "26") (pinfunction "VOUT_26") (pintype "unspecified"))
    )
    (net (code "93") (name "Net-(U12-RF_IN)") (class "Default")
      (node (ref "U12") (pin "11") (pinfunction "RF_IN_11") (pintype "unspecified"))
      (node (ref "U13") (pin "6") (pinfunction "RFOUT_6") (pintype "unspecified"))
    )
    (net (code "94") (name "Net-(U13-RFIN)") (class "Default")
      (node (ref "L3") (pin "2") (pinfunction "2_2") (pintype "unspecified"))
      (node (ref "U13") (pin "3") (pinfunction "RFIN_3") (pintype "unspecified"))
    )
    (net (code "95") (name "Net-(U15-C1)") (class "Default")
      (node (ref "U15") (pin "10") (pinfunction "C1_10") (pintype "unspecified"))
      (node (ref "U18") (pin "1") (pinfunction "1_1") (pintype "unspecified"))
    )
    (net (code "96") (name "Net-(U15-SETC)") (class "Default")
      (node (ref "U15") (pin "12") (pinfunction "SETC_12") (pintype "unspecified"))
      (node (ref "U17") (pin "1") (pinfunction "1_1") (pintype "unspecified"))
    )
    (net (code "97") (name "Net-(U15-SETP)") (class "Default")
      (node (ref "U15") (pin "8") (pinfunction "SETP_8") (pintype "unspecified"))
      (node (ref "U17") (pin "2") (pinfunction "2_2") (pintype "unspecified"))
    )
    (net (code "98") (name "VBAT+") (class "Default")
      (node (ref "C14") (pin "2") (pinfunction "2_2") (pintype "unspecified"))
      (node (ref "C15") (pin "2") (pinfunction "2_2") (pintype "unspecified"))
      (node (ref "C8") (pin "2") (pinfunction "2_2") (pintype "unspecified"))
      (node (ref "C9") (pin "2") (pinfunction "2_2") (pintype "unspecified"))
      (node (ref "CN1") (pin "2") (pinfunction "2_2") (pintype "unspecified"))
      (node (ref "CN2") (pin "2") (pinfunction "2_2") (pintype "unspecified"))
      (node (ref "R1") (pin "2") (pinfunction "2_2") (pintype "unspecified"))
      (node (ref "R17") (pin "2") (pinfunction "2_2") (pintype "unspecified"))
      (node (ref "R9") (pin "2") (pinfunction "2_2") (pintype "unspecified"))
      (node (ref "U12") (pin "6") (pinfunction "VBAT_6") (pintype "unspecified"))
      (node (ref "U2") (pin "7") (pinfunction "IN_7") (pintype "unspecified"))
      (node (ref "U4") (pin "7") (pinfunction "IN_7") (pintype "unspecified"))
    )
    (net (code "99") (name "VDD") (class "Default")
      (node (ref "C2") (pin "2") (pinfunction "2_2") (pintype "unspecified"))
      (node (ref "C3") (pin "2") (pinfunction "2_2") (pintype "unspecified"))
      (node (ref "C30") (pin "2") (pinfunction "2_2") (pintype "unspecified"))
      (node (ref "C32") (pin "2") (pinfunction "2_2") (pintype "unspecified"))
      (node (ref "C33") (pin "2") (pinfunction "2_2") (pintype "unspecified"))
      (node (ref "C35") (pin "1") (pinfunction "1_1") (pintype "unspecified"))
      (node (ref "C4") (pin "2") (pinfunction "2_2") (pintype "unspecified"))
      (node (ref "C5") (pin "2") (pinfunction "2_2") (pintype "unspecified"))
      (node (ref "C6") (pin "2") (pinfunction "2_2") (pintype "unspecified"))
      (node (ref "C7") (pin "2") (pinfunction "2_2") (pintype "unspecified"))
      (node (ref "H6") (pin "1") (pinfunction "1_1") (pintype "unspecified"))
      (node (ref "R11") (pin "2") (pinfunction "2_2") (pintype "unspecified"))
      (node (ref "R28") (pin "2") (pinfunction "2_2") (pintype "unspecified"))
      (node (ref "R29") (pin "2") (pinfunction "2_2") (pintype "unspecified"))
      (node (ref "R3") (pin "2") (pinfunction "2_2") (pintype "unspecified"))
      (node (ref "SW1") (pin "1") (pinfunction "1_1") (pintype "unspecified"))
      (node (ref "SW1") (pin "3") (pinfunction "3_3") (pintype "unspecified"))
      (node (ref "U10") (pin "3") (pinfunction "#WP/IO2_3") (pintype "unspecified"))
      (node (ref "U10") (pin "7") (pinfunction "#HOLD/IO3_7") (pintype "unspecified"))
      (node (ref "U10") (pin "8") (pinfunction "VCC_8") (pintype "unspecified"))
      (node (ref "U3") (pin "100") (pinfunction "VDD_100") (pintype "unspecified"))
      (node (ref "U3") (pin "11") (pinfunction "VDD_11") (pintype "unspecified"))
      (node (ref "U3") (pin "21") (pinfunction "VREF+_21") (pintype "unspecified"))
      (node (ref "U3") (pin "22") (pinfunction "VDDA_22") (pintype "unspecified"))
      (node (ref "U3") (pin "28") (pinfunction "VDD_28") (pintype "unspecified"))
      (node (ref "U3") (pin "50") (pinfunction "VDD_50") (pintype "unspecified"))
      (node (ref "U3") (pin "6") (pinfunction "VBAT_6") (pintype "unspecified"))
      (node (ref "U3") (pin "75") (pinfunction "VDD_75") (pintype "unspecified"))
      (node (ref "U7") (pin "5") (pinfunction "VOUT_5") (pintype "unspecified"))
      (node (ref "U9") (pin "2") (pinfunction "CSB_2") (pintype "unspecified"))
      (node (ref "U9") (pin "6") (pinfunction "VDDIO_6") (pintype "unspecified"))
      (node (ref "U9") (pin "8") (pinfunction "VDD_8") (pintype "unspecified"))
    )
    (net (code "100") (name "unconnected-(CN1-Pad7)") (class "Default")
      (node (ref "CN1") (pin "7") (pinfunction "7_7") (pintype "unspecified+no_connect"))
    )
    (net (code "101") (name "unconnected-(CN1-Pad8)") (class "Default")
      (node (ref "CN1") (pin "8") (pinfunction "8_8") (pintype "unspecified+no_connect"))
    )
    (net (code "102") (name "unconnected-(CN2-Pad7)") (class "Default")
      (node (ref "CN2") (pin "7") (pinfunction "7_7") (pintype "unspecified+no_connect"))
    )
    (net (code "103") (name "unconnected-(SDO1-RESV-Pad2)") (class "Default")
      (node (ref "SDO1") (pin "2") (pinfunction "RESV_2") (pintype "unspecified+no_connect"))
    )
    (net (code "104") (name "unconnected-(SDO1-RESV-Pad3)") (class "Default")
      (node (ref "SDO1") (pin "3") (pinfunction "RESV_3") (pintype "unspecified+no_connect"))
    )
    (net (code "105") (name "unconnected-(SDO1-RESV-Pad10)") (class "Default")
      (node (ref "SDO1") (pin "10") (pinfunction "RESV_10") (pintype "unspecified+no_connect"))
    )
    (net (code "106") (name "unconnected-(SDO1-RESV-Pad11)") (class "Default")
      (node (ref "SDO1") (pin "11") (pinfunction "RESV_11") (pintype "unspecified+no_connect"))
    )
    (net (code "107") (name "unconnected-(U3-NC-Pad19)") (class "Default")
      (node (ref "U3") (pin "19") (pinfunction "NC_19") (pintype "unspecified+no_connect"))
    )
    (net (code "108") (name "unconnected-(U3-PA8-Pad67)") (class "Default")
      (node (ref "U3") (pin "67") (pinfunction "PA8_67") (pintype "unspecified+no_connect"))
    )
    (net (code "109") (name "unconnected-(U3-PB4-Pad90)") (class "Default")
      (node (ref "U3") (pin "90") (pinfunction "PB4_90") (pintype "unspecified+no_connect"))
    )
    (net (code "110") (name "unconnected-(U3-PB5-Pad91)") (class "Default")
      (node (ref "U3") (pin "91") (pinfunction "PB5_91") (pintype "unspecified+no_connect"))
    )
    (net (code "111") (name "unconnected-(U3-PB12-Pad51)") (class "Default")
      (node (ref "U3") (pin "51") (pinfunction "PB12_51") (pintype "unspecified+no_connect"))
    )
    (net (code "112") (name "unconnected-(U3-PB13-Pad52)") (class "Default")
      (node (ref "U3") (pin "52") (pinfunction "PB13_52") (pintype "unspecified+no_connect"))
    )
    (net (code "113") (name "unconnected-(U3-PB14-Pad53)") (class "Default")
      (node (ref "U3") (pin "53") (pinfunction "PB14_53") (pintype "unspecified+no_connect"))
    )
    (net (code "114") (name "unconnected-(U3-PB15-Pad54)") (class "Default")
      (node (ref "U3") (pin "54") (pinfunction "PB15_54") (pintype "unspecified+no_connect"))
    )
    (net (code "115") (name "unconnected-(U3-PC13-Pad7)") (class "Default")
      (node (ref "U3") (pin "7") (pinfunction "PC13_7") (pintype "unspecified+no_connect"))
    )
    (net (code "116") (name "unconnected-(U3-PC14-Pad8)") (class "Default")
      (node (ref "U3") (pin "8") (pinfunction "PC14_8") (pintype "unspecified+no_connect"))
    )
    (net (code "117") (name "unconnected-(U3-PC15-Pad9)") (class "Default")
      (node (ref "U3") (pin "9") (pinfunction "PC15_9") (pintype "unspecified+no_connect"))
    )
    (net (code "118") (name "unconnected-(U3-PD0-Pad81)") (class "Default")
      (node (ref "U3") (pin "81") (pinfunction "PD0_81") (pintype "unspecified+no_connect"))
    )
    (net (code "119") (name "unconnected-(U3-PD2-Pad83)") (class "Default")
      (node (ref "U3") (pin "83") (pinfunction "PD2_83") (pintype "unspecified+no_connect"))
    )
    (net (code "120") (name "unconnected-(U3-PD7-Pad88)") (class "Default")
      (node (ref "U3") (pin "88") (pinfunction "PD7_88") (pintype "unspecified+no_connect"))
    )
    (net (code "121") (name "unconnected-(U3-PD8-Pad55)") (class "Default")
      (node (ref "U3") (pin "55") (pinfunction "PD8_55") (pintype "unspecified+no_connect"))
    )
    (net (code "122") (name "unconnected-(U3-PD9-Pad56)") (class "Default")
      (node (ref "U3") (pin "56") (pinfunction "PD9_56") (pintype "unspecified+no_connect"))
    )
    (net (code "123") (name "unconnected-(U3-PD10-Pad57)") (class "Default")
      (node (ref "U3") (pin "57") (pinfunction "PD10_57") (pintype "unspecified+no_connect"))
    )
    (net (code "124") (name "unconnected-(U3-PD11-Pad58)") (class "Default")
      (node (ref "U3") (pin "58") (pinfunction "PD11_58") (pintype "unspecified+no_connect"))
    )
    (net (code "125") (name "unconnected-(U3-PD12-Pad59)") (class "Default")
      (node (ref "U3") (pin "59") (pinfunction "PD12_59") (pintype "unspecified+no_connect"))
    )
    (net (code "126") (name "unconnected-(U3-PE0-Pad97)") (class "Default")
      (node (ref "U3") (pin "97") (pinfunction "PE0_97") (pintype "unspecified+no_connect"))
    )
    (net (code "127") (name "unconnected-(U3-PE1-Pad98)") (class "Default")
      (node (ref "U3") (pin "98") (pinfunction "PE1_98") (pintype "unspecified+no_connect"))
    )
    (net (code "128") (name "unconnected-(U3-PE2-Pad1)") (class "Default")
      (node (ref "U3") (pin "1") (pinfunction "PE2_1") (pintype "unspecified+no_connect"))
    )
    (net (code "129") (name "unconnected-(U3-PE3-Pad2)") (class "Default")
      (node (ref "U3") (pin "2") (pinfunction "PE3_2") (pintype "unspecified+no_connect"))
    )
    (net (code "130") (name "unconnected-(U3-PE4-Pad3)") (class "Default")
      (node (ref "U3") (pin "3") (pinfunction "PE4_3") (pintype "unspecified+no_connect"))
    )
    (net (code "131") (name "unconnected-(U3-PE5-Pad4)") (class "Default")
      (node (ref "U3") (pin "4") (pinfunction "PE5_4") (pintype "unspecified+no_connect"))
    )
    (net (code "132") (name "unconnected-(U3-PE6-Pad5)") (class "Default")
      (node (ref "U3") (pin "5") (pinfunction "PE6_5") (pintype "unspecified+no_connect"))
    )
    (net (code "133") (name "unconnected-(U3-PE7-Pad38)") (class "Default")
      (node (ref "U3") (pin "38") (pinfunction "PE7_38") (pintype "unspecified+no_connect"))
    )
    (net (code "134") (name "unconnected-(U3-PE8-Pad39)") (class "Default")
      (node (ref "U3") (pin "39") (pinfunction "PE8_39") (pintype "unspecified+no_connect"))
    )
    (net (code "135") (name "unconnected-(U3-PE9-Pad40)") (class "Default")
      (node (ref "U3") (pin "40") (pinfunction "PE9_40") (pintype "unspecified+no_connect"))
    )
    (net (code "136") (name "unconnected-(U3-PE10-Pad41)") (class "Default")
      (node (ref "U3") (pin "41") (pinfunction "PE10_41") (pintype "unspecified+no_connect"))
    )
    (net (code "137") (name "unconnected-(U3-PE11-Pad42)") (class "Default")
      (node (ref "U3") (pin "42") (pinfunction "PE11_42") (pintype "unspecified+no_connect"))
    )
    (net (code "138") (name "unconnected-(U3-PE12-Pad43)") (class "Default")
      (node (ref "U3") (pin "43") (pinfunction "PE12_43") (pintype "unspecified+no_connect"))
    )
    (net (code "139") (name "unconnected-(U3-PE13-Pad44)") (class "Default")
      (node (ref "U3") (pin "44") (pinfunction "PE13_44") (pintype "unspecified+no_connect"))
    )
    (net (code "140") (name "unconnected-(U3-PE14-Pad45)") (class "Default")
      (node (ref "U3") (pin "45") (pinfunction "PE14_45") (pintype "unspecified+no_connect"))
    )
    (net (code "141") (name "unconnected-(U3-PE15-Pad46)") (class "Default")
      (node (ref "U3") (pin "46") (pinfunction "PE15_46") (pintype "unspecified+no_connect"))
    )
    (net (code "142") (name "unconnected-(U3-PH3-Pad49)") (class "Default")
      (node (ref "U3") (pin "49") (pinfunction "PH3_49") (pintype "unspecified+no_connect"))
    )
    (net (code "143") (name "unconnected-(U6-CLKOUT-Pad7)") (class "Default")
      (node (ref "U6") (pin "7") (pinfunction "CLKOUT_7") (pintype "unspecified+no_connect"))
    )
    (net (code "144") (name "unconnected-(U6-HSYNC-Pad18)") (class "Default")
      (node (ref "U6") (pin "18") (pinfunction "HSYNC_18") (pintype "unspecified+no_connect"))
    )
    (net (code "145") (name "unconnected-(U6-LOS-Pad12)") (class "Default")
      (node (ref "U6") (pin "12") (pinfunction "LOS_12") (pintype "unspecified+no_connect"))
    )
    (net (code "146") (name "unconnected-(U6-NC-Pad1)") (class "Default")
      (node (ref "U6") (pin "1") (pinfunction "NC_1") (pintype "unspecified+no_connect"))
    )
    (net (code "147") (name "unconnected-(U6-NC-Pad2)") (class "Default")
      (node (ref "U6") (pin "2") (pinfunction "NC_2") (pintype "unspecified+no_connect"))
    )
    (net (code "148") (name "unconnected-(U6-NC-Pad13)") (class "Default")
      (node (ref "U6") (pin "13") (pinfunction "NC_13") (pintype "unspecified+no_connect"))
    )
    (net (code "149") (name "unconnected-(U6-NC-Pad14)") (class "Default")
      (node (ref "U6") (pin "14") (pinfunction "NC_14") (pintype "unspecified+no_connect"))
    )
    (net (code "150") (name "unconnected-(U6-NC-Pad15)") (class "Default")
      (node (ref "U6") (pin "15") (pinfunction "NC_15") (pintype "unspecified+no_connect"))
    )
    (net (code "151") (name "unconnected-(U6-NC-Pad16)") (class "Default")
      (node (ref "U6") (pin "16") (pinfunction "NC_16") (pintype "unspecified+no_connect"))
    )
    (net (code "152") (name "unconnected-(U6-NC-Pad27)") (class "Default")
      (node (ref "U6") (pin "27") (pinfunction "NC_27") (pintype "unspecified+no_connect"))
    )
    (net (code "153") (name "unconnected-(U6-NC-Pad28)") (class "Default")
      (node (ref "U6") (pin "28") (pinfunction "NC_28") (pintype "unspecified+no_connect"))
    )
    (net (code "154") (name "unconnected-(U6-VSYNC-Pad17)") (class "Default")
      (node (ref "U6") (pin "17") (pinfunction "VSYNC_17") (pintype "unspecified+no_connect"))
    )
    (net (code "155") (name "unconnected-(U7-NC-Pad4)") (class "Default")
      (node (ref "U7") (pin "4") (pinfunction "NC_4") (pintype "unspecified+no_connect"))
    )
    (net (code "156") (name "unconnected-(U8-NC-Pad4)") (class "Default")
      (node (ref "U8") (pin "4") (pinfunction "NC_4") (pintype "unspecified+no_connect"))
    )
    (net (code "157") (name "unconnected-(U12-1PPS-Pad4)") (class "Default")
      (node (ref "U12") (pin "4") (pinfunction "1PPS_4") (pintype "unspecified+no_connect"))
    )
    (net (code "158") (name "unconnected-(U12-NC-Pad7)") (class "Default")
      (node (ref "U12") (pin "7") (pinfunction "NC_7") (pintype "unspecified+no_connect"))
    )
    (net (code "159") (name "unconnected-(U12-NC-Pad13)") (class "Default")
      (node (ref "U12") (pin "13") (pinfunction "NC_13") (pintype "unspecified+no_connect"))
    )
    (net (code "160") (name "unconnected-(U12-NRESET-Pad9)") (class "Default")
      (node (ref "U12") (pin "9") (pinfunction "NRESET_9") (pintype "unspecified+no_connect"))
    )
    (net (code "161") (name "unconnected-(U12-ON{slash}OFF-Pad5)") (class "Default")
      (node (ref "U12") (pin "5") (pinfunction "ON/OFF_5") (pintype "unspecified+no_connect"))
    )
    (net (code "162") (name "unconnected-(U12-Reserved-Pad15)") (class "Default")
      (node (ref "U12") (pin "15") (pinfunction "Reserved_15") (pintype "unspecified+no_connect"))
    )
    (net (code "163") (name "unconnected-(U12-Reserved-Pad18)") (class "Default")
      (node (ref "U12") (pin "18") (pinfunction "Reserved_18") (pintype "unspecified+no_connect"))
    )
    (net (code "164") (name "unconnected-(U12-SCL-Pad17)") (class "Default")
      (node (ref "U12") (pin "17") (pinfunction "SCL_17") (pintype "unspecified+no_connect"))
    )
    (net (code "165") (name "unconnected-(U12-SDA-Pad16)") (class "Default")
      (node (ref "U12") (pin "16") (pinfunction "SDA_16") (pintype "unspecified+no_connect"))
    )
    (net (code "166") (name "unconnected-(U12-VCC_RF-Pad14)") (class "Default")
      (node (ref "U12") (pin "14") (pinfunction "VCC_RF_14") (pintype "unspecified+no_connect"))
    )
    (net (code "167") (name "unconnected-(U15-DRDY-Pad15)") (class "Default")
      (node (ref "U15") (pin "15") (pinfunction "DRDY_15") (pintype "unspecified+no_connect"))
    )
    (net (code "168") (name "unconnected-(U15-NC-Pad3)") (class "Default")
      (node (ref "U15") (pin "3") (pinfunction "NC_3") (pintype "unspecified+no_connect"))
    )
    (net (code "169") (name "unconnected-(U15-NC-Pad5)") (class "Default")
      (node (ref "U15") (pin "5") (pinfunction "NC_5") (pintype "unspecified+no_connect"))
    )
    (net (code "170") (name "unconnected-(U15-NC-Pad6)") (class "Default")
      (node (ref "U15") (pin "6") (pinfunction "NC_6") (pintype "unspecified+no_connect"))
    )
    (net (code "171") (name "unconnected-(U15-NC-Pad7)") (class "Default")
      (node (ref "U15") (pin "7") (pinfunction "NC_7") (pintype "unspecified+no_connect"))
    )
    (net (code "172") (name "unconnected-(U15-NC-Pad14)") (class "Default")
      (node (ref "U15") (pin "14") (pinfunction "NC_14") (pintype "unspecified+no_connect"))
    )
    (net (code "173") (name "unconnected-(USB1-CC1-PadA5)") (class "Default")
      (node (ref "USB1") (pin "A5") (pinfunction "CC1_A5") (pintype "unspecified+no_connect"))
    )
    (net (code "174") (name "unconnected-(USB1-CC2-PadB5)") (class "Default")
      (node (ref "USB1") (pin "B5") (pinfunction "CC2_B5") (pintype "unspecified+no_connect"))
    )
    (net (code "175") (name "unconnected-(USB1-SUB1-PadA8)") (class "Default")
      (node (ref "USB1") (pin "A8") (pinfunction "SUB1_A8") (pintype "unspecified+no_connect"))
    )
    (net (code "176") (name "unconnected-(USB1-SUB2-PadB8)") (class "Default")
      (node (ref "USB1") (pin "B8") (pinfunction "SUB2_B8") (pintype "unspecified+no_connect"))
    )
  )
)
